# Sens_rler.net
KiCad netlist of a schematic drawn in Altium Designer
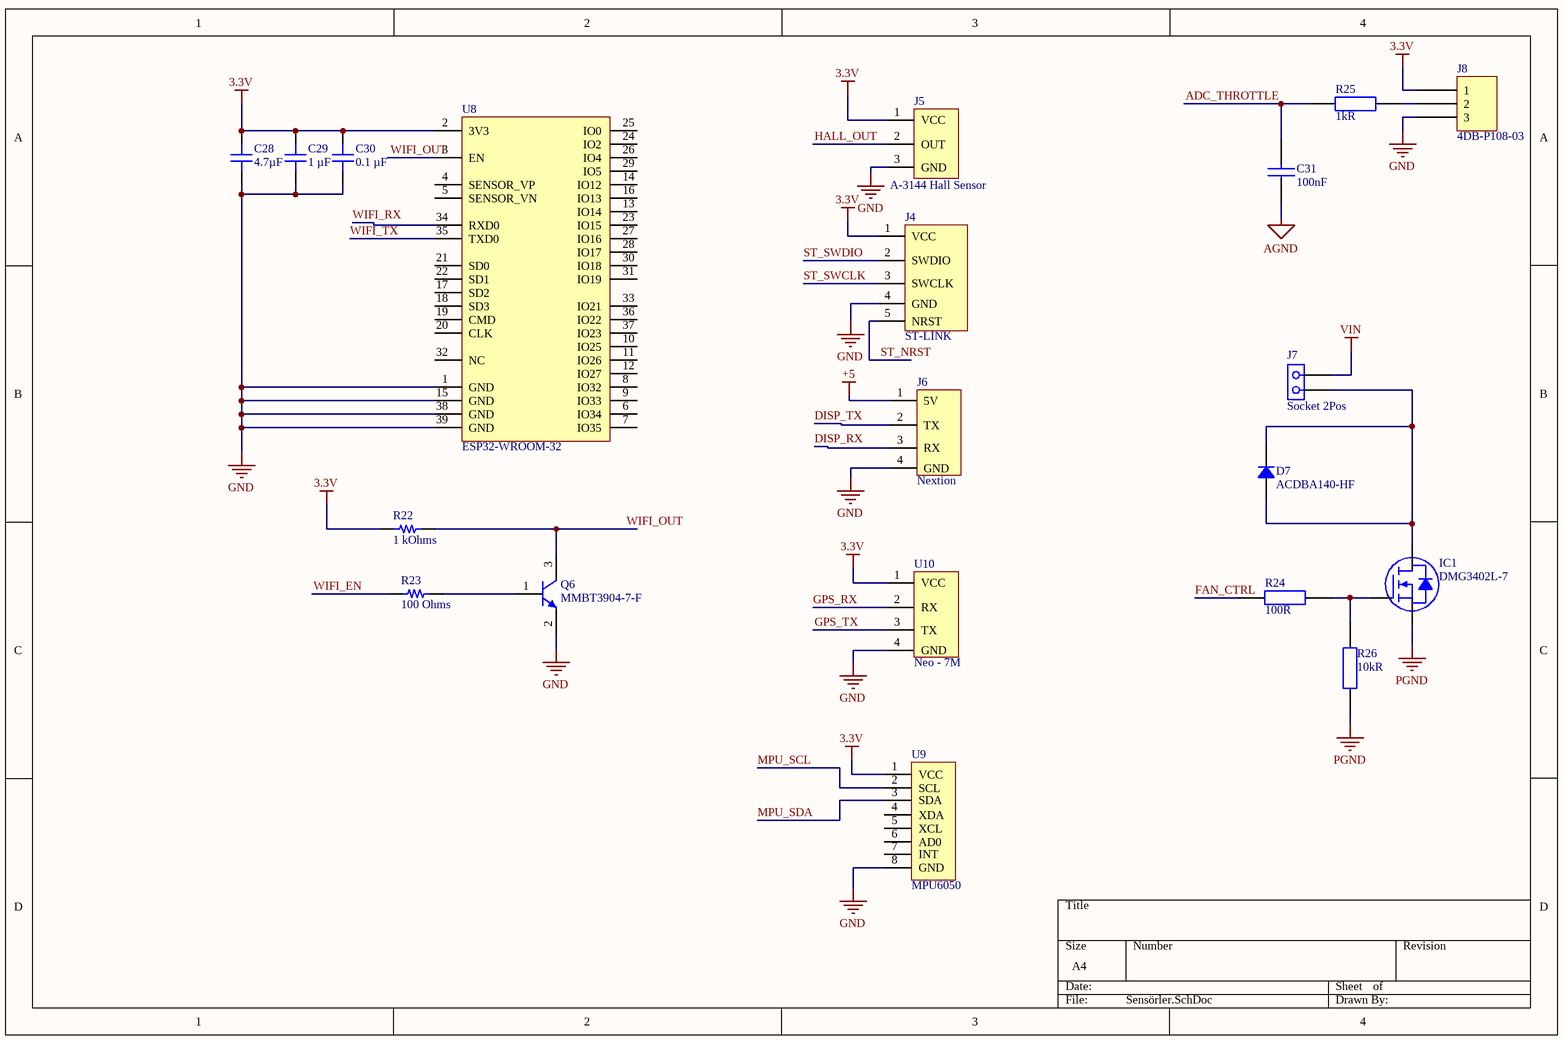
[diagram p0: Sensörler.SchDoc]

(export (version "E")
  (design (tool "Eeschema 10.0.6"))
  (components
    (comp (ref "C28")
      (value "4.7µF")
      (footprint "CAP 0805_2012")
      (description "CAP CER 4.7UF 16V X5R 0805")
      (fields
        (field (name "PART NUMBER") "0805YD475MAT2A")
        (field (name "CAPACITANCE") "4.7µF")
        (field (name "MANUFACTURER") "AVX Corporation")
      )
      (libsource (lib "Celestial Altium Library - altium_library") (part "Capacitor"))
    )
    (comp (ref "C29")
      (value "1 µF")
      (footprint "CAP 0805_2012")
      (description "CAP CER 1UF 16V X7R 0805")
      (fields
        (field (name "PART NUMBER") "EMK212B7105KGHTR")
        (field (name "CAPACITANCE") "1 µF")
        (field (name "MANUFACTURER") "Taiyo Yuden")
      )
      (libsource (lib "Celestial Altium Library - altium_library") (part "Capacitor"))
    )
    (comp (ref "C30")
      (value "0.1 µF")
      (footprint "CAP 0805_2012")
      (description "CAP CER 0.1UF 16V X7R 0805")
      (fields
        (field (name "PART NUMBER") "0805B104K160CT")
        (field (name "CAPACITANCE") "0.1 µF")
        (field (name "MANUFACTURER") "Walsin Technology Corporation")
      )
      (libsource (lib "Celestial Altium Library - altium_library") (part "Capacitor"))
    )
    (comp (ref "C31")
      (value "CL21B104KBCNNNC")
      (footprint "CAP_0805")
      (description "CAP CER 100nF %10 0805")
      (fields
        (field (name "MANUFACTURER") "Samsung")
        (field (name "TOLERANCE") "10%")
        (field (name "CAPACITANCE") "100nF")
        (field (name "DESIGNED BY") "BERK")
      )
      (libsource (lib "UDEMY_Library") (part "CAP CER 100nF 0805"))
    )
    (comp (ref "D7")
      (value "ACDBA140-HF")
      (footprint "DO214AC SMA")
      (description "DIODE SCHOTTKY 40V 1A DO214AC")
      (fields (field (name "MANUFACTURER") "Comchip Technology"))
      (libsource (lib "Celestial Altium Library - altium_library") (part "Diode"))
    )
    (comp (ref "IC1")
      (value "DMG3402L-7")
      (footprint "DIODES SOT-23-3")
      (description "MOSFET N-CH 30V 4A SOT23")
      (fields (field (name "MANUFACTURER") "Diodes Incorporated"))
      (libsource (lib "Celestial Altium Library - altium_library") (part "DIODES INC MOSFET N-CH SOT-23-3"))
    )
    (comp (ref "J4") (value "ST-LİNK") (footprint "ST-LİNK") (libsource (lib "TIDA_00620") (part "ST-LİNK")))
    (comp (ref "J5")
      (value "A-3144 Hall Sensor")
      (footprint "A-3144")
      (libsource (lib "TIDA_00620") (part "A-3144 Hall Sensor"))
    )
    (comp (ref "J6") (value "Nextion") (footprint "Nextion") (libsource (lib "TIDA_00620") (part "Nextion")))
    (comp (ref "J7")
      (value "Socket 2Pos")
      (footprint "691101710002")
      (description "Conn Terminal Block 2 POS 5mm Solder ST Thru-Hole 16A Box")
      (fields
        (field (name "MANUFACTURER") "Wurth Elektronik")
        (field (name "MANUFACTURER PART NUMBER") "691101710002")
      )
      (libsource (lib "TIDA_00620") (part "691 101 710 002"))
    )
    (comp (ref "J8")
      (value "4DB-P108-03")
      (footprint "TE 4DB-P108-03")
      (description "CONN BARRIER STRIP 3CIRC 0.325\"")
      (fields (field (name "MANUFACTURER") "TE Connectivity AMP Connectors"))
      (libsource (lib "Celestial Altium Library - altium_library") (part "3 Pin"))
    )
    (comp (ref "Q6")
      (value "MMBT3904-7-F")
      (footprint "DIODES SOT-23-3")
      (description "TRANS NPN 40V 0.2A SOT23-3")
      (fields (field (name "MANUFACTURER") "Diodes Incorporated"))
      (libsource (lib "Celestial Altium Library - altium_library") (part "DIODES INC NPN SOT-23-3"))
    )
    (comp (ref "R22")
      (value "1 kOhms")
      (footprint "RES 0603_1608")
      (description "RES SMD 1K OHM 0.1% 1/16W 0603")
      (fields
        (field (name "PART NUMBER") "CPF0603B1K0E")
        (field (name "MANUFACTURER") "TE Connectivity Passive Product")
      )
      (libsource (lib "Celestial Altium Library - altium_library") (part "Resistor"))
    )
    (comp (ref "R23")
      (value "100 Ohms")
      (footprint "RES 0402_1005")
      (description "RES 100 OHM 0.5% 1/5W 0402")
      (fields
        (field (name "PART NUMBER") "MCS0402PD1000DE500")
        (field (name "MANUFACTURER") "Vishay Beyschlag")
      )
      (libsource (lib "Celestial Altium Library - altium_library") (part "Resistor"))
    )
    (comp (ref "R24")
      (value "RC0603JR-07100RL")
      (footprint "RES_0603")
      (description "RES 100 %5 OHM 0603 SMD")
      (fields
        (field (name "MANUFACTURER") "Yageo")
        (field (name "TOLERANCE") "5%")
        (field (name "RESISTANCE") "100R")
        (field (name "DESIGNED BY") "BERK")
      )
      (libsource (lib "UDEMY_Library") (part "RES 100 OHM 0603"))
    )
    (comp (ref "R25")
      (value "RC0603FR-0710KL")
      (footprint "RES_0603")
      (description "RES 1K %1 OHM 0603 SMD")
      (fields
        (field (name "MANUFACTURER") "Yageo")
        (field (name "MANUFACTURER PART NUMBER") "RC0603JR-071KL")
        (field (name "RESISTANCE") "1kR")
        (field (name "DESIGNED BY") "BERK")
      )
      (libsource (lib "UDEMY_Library") (part "RES 1K OHM 0603"))
    )
    (comp (ref "R26")
      (value "RC0603FR-0710KL")
      (footprint "RES_0603")
      (description "RES 10K %1 OHM 0603 SMD")
      (fields
        (field (name "MANUFACTURER") "Yageo")
        (field (name "TOLERANCE") "1%")
        (field (name "RESISTANCE") "10kR")
        (field (name "DESIGNED BY") "BERK")
      )
      (libsource (lib "UDEMY_Library") (part "RES 10K OHM 0603"))
    )
    (comp (ref "U8")
      (value "ESP32-WROOM-32")
      (footprint "ESP32-32")
      (libsource (lib "TIDA_00620") (part "ESP32-WROOM-32"))
    )
    (comp (ref "U9")
      (value "MPU6050")
      (footprint "MPU6050")
      (description "IMU (Inertial Measurement Unit), 6-Axis, Accelerometer, Gyroscope")
      (fields (field (name "MANUFACTURER") "InvenSense") (field (name "MANUFACTURER PART NUMBER") "MPU-6050"))
      (libsource (lib "TIDA_00620") (part "MPU6050"))
    )
    (comp (ref "U10")
      (value "Neo - 7M")
      (footprint "Neo - 7M")
      (libsource (lib "TIDA_00620") (part "Neo - 7M"))
    )
  )
  (nets
    (net (code "1") (name "+5") (class "Default")
      (node (ref "J6") (pin "1") (pinfunction "5V_1") (pintype "power_in"))
    )
    (net (code "2") (name "/ADC_THROTTLE") (class "Default")
      (node (ref "C31") (pin "2") (pinfunction "2_2") (pintype "passive"))
      (node (ref "R25") (pin "1") (pinfunction "1_1") (pintype "passive"))
    )
    (net (code "3") (name "/DISP_RX") (class "Default")
      (node (ref "J6") (pin "3") (pinfunction "RX_3") (pintype "passive"))
    )
    (net (code "4") (name "/DISP_TX") (class "Default")
      (node (ref "J6") (pin "2") (pinfunction "TX_2") (pintype "passive"))
    )
    (net (code "5") (name "/FAN_CTRL") (class "Default")
      (node (ref "R24") (pin "1") (pinfunction "1_1") (pintype "passive"))
    )
    (net (code "6") (name "/GPS_RX") (class "Default")
      (node (ref "U10") (pin "2") (pinfunction "RX_2") (pintype "passive"))
    )
    (net (code "7") (name "/GPS_TX") (class "Default")
      (node (ref "U10") (pin "3") (pinfunction "TX_3") (pintype "passive"))
    )
    (net (code "8") (name "/HALL_OUT") (class "Default")
      (node (ref "J5") (pin "2") (pinfunction "OUT_2") (pintype "passive"))
    )
    (net (code "9") (name "/MPU_SCL") (class "Default")
      (node (ref "U9") (pin "2") (pinfunction "SCL_2") (pintype "passive"))
    )
    (net (code "10") (name "/MPU_SDA") (class "Default")
      (node (ref "U9") (pin "3") (pinfunction "SDA_3") (pintype "passive"))
    )
    (net (code "11") (name "/ST_NRST") (class "Default")
      (node (ref "J4") (pin "5") (pinfunction "NRST_5") (pintype "passive"))
    )
    (net (code "12") (name "/ST_SWCLK") (class "Default")
      (node (ref "J4") (pin "3") (pinfunction "SWCLK_3") (pintype "passive"))
    )
    (net (code "13") (name "/ST_SWDIO") (class "Default")
      (node (ref "J4") (pin "2") (pinfunction "SWDIO_2") (pintype "passive"))
    )
    (net (code "14") (name "/WIFI_EN") (class "Default")
      (node (ref "R23") (pin "1") (pinfunction "1_1") (pintype "passive"))
    )
    (net (code "15") (name "/WIFI_OUT") (class "Default")
      (node (ref "Q6") (pin "3") (pinfunction "C_3") (pintype "passive"))
      (node (ref "R22") (pin "2") (pinfunction "2_2") (pintype "passive"))
      (node (ref "U8") (pin "3") (pinfunction "EN_3") (pintype "passive"))
    )
    (net (code "16") (name "/WIFI_RX") (class "Default")
      (node (ref "U8") (pin "34") (pinfunction "RXD0_34") (pintype "passive"))
    )
    (net (code "17") (name "/WIFI_TX") (class "Default")
      (node (ref "U8") (pin "35") (pinfunction "TXD0_35") (pintype "passive"))
    )
    (net (code "18") (name "3.3V") (class "Default")
      (node (ref "C28") (pin "2") (pinfunction "2_2") (pintype "passive"))
      (node (ref "C29") (pin "2") (pinfunction "2_2") (pintype "passive"))
      (node (ref "C30") (pin "2") (pinfunction "2_2") (pintype "passive"))
      (node (ref "J4") (pin "1") (pinfunction "VCC_1") (pintype "passive"))
      (node (ref "J5") (pin "1") (pinfunction "VCC_1") (pintype "passive"))
      (node (ref "J8") (pin "1") (pinfunction "1_1") (pintype "passive"))
      (node (ref "R22") (pin "1") (pinfunction "1_1") (pintype "passive"))
      (node (ref "U10") (pin "1") (pinfunction "VCC_1") (pintype "passive"))
      (node (ref "U8") (pin "2") (pinfunction "3V3_2") (pintype "passive"))
      (node (ref "U9") (pin "1") (pinfunction "VCC_1") (pintype "power_in"))
    )
    (net (code "19") (name "AGND") (class "Default")
      (node (ref "C31") (pin "1") (pinfunction "1_1") (pintype "passive"))
    )
    (net (code "20") (name "GND") (class "Default")
      (node (ref "C28") (pin "1") (pinfunction "1_1") (pintype "passive"))
      (node (ref "C29") (pin "1") (pinfunction "1_1") (pintype "passive"))
      (node (ref "C30") (pin "1") (pinfunction "1_1") (pintype "passive"))
      (node (ref "J4") (pin "4") (pinfunction "GND_4") (pintype "passive"))
      (node (ref "J5") (pin "3") (pinfunction "GND_3") (pintype "passive"))
      (node (ref "J6") (pin "4") (pinfunction "GND_4") (pintype "passive"))
      (node (ref "J8") (pin "3") (pinfunction "3_3") (pintype "passive"))
      (node (ref "Q6") (pin "2") (pinfunction "E_2") (pintype "passive"))
      (node (ref "U10") (pin "4") (pinfunction "GND_4") (pintype "passive"))
      (node (ref "U8") (pin "1") (pinfunction "GND_1") (pintype "passive"))
      (node (ref "U8") (pin "15") (pinfunction "GND_15") (pintype "passive"))
      (node (ref "U8") (pin "38") (pinfunction "GND_38") (pintype "passive"))
      (node (ref "U8") (pin "39") (pinfunction "GND_39") (pintype "passive"))
      (node (ref "U9") (pin "8") (pinfunction "GND_8") (pintype "power_in"))
    )
    (net (code "21") (name "Net-(IC1-D)") (class "Default")
      (node (ref "D7") (pin "1") (pinfunction "1_1") (pintype "passive"))
      (node (ref "D7") (pin "2") (pinfunction "2_2") (pintype "passive"))
      (node (ref "IC1") (pin "3") (pinfunction "D_3") (pintype "passive"))
      (node (ref "J7") (pin "1") (pinfunction "1_1") (pintype "passive"))
    )
    (net (code "22") (name "Net-(IC1-G)") (class "Default")
      (node (ref "IC1") (pin "1") (pinfunction "G_1") (pintype "passive"))
      (node (ref "R24") (pin "2") (pinfunction "2_2") (pintype "passive"))
      (node (ref "R26") (pin "2") (pinfunction "2_2") (pintype "passive"))
    )
    (net (code "23") (name "Net-(J8-Pad2)") (class "Default")
      (node (ref "J8") (pin "2") (pinfunction "2_2") (pintype "passive"))
      (node (ref "R25") (pin "2") (pinfunction "2_2") (pintype "passive"))
    )
    (net (code "24") (name "Net-(Q6-B)") (class "Default")
      (node (ref "Q6") (pin "1") (pinfunction "B_1") (pintype "passive"))
      (node (ref "R23") (pin "2") (pinfunction "2_2") (pintype "passive"))
    )
    (net (code "25") (name "PGND") (class "Default")
      (node (ref "IC1") (pin "2") (pinfunction "S_2") (pintype "passive"))
      (node (ref "R26") (pin "1") (pinfunction "1_1") (pintype "passive"))
    )
    (net (code "26") (name "VIN") (class "Default")
      (node (ref "J7") (pin "2") (pinfunction "2_2") (pintype "passive"))
    )
    (net (code "27") (name "unconnected-(U8-CLK-Pad20)") (class "Default")
      (node (ref "U8") (pin "20") (pinfunction "CLK_20") (pintype "passive"))
    )
    (net (code "28") (name "unconnected-(U8-CMD-Pad19)") (class "Default")
      (node (ref "U8") (pin "19") (pinfunction "CMD_19") (pintype "passive"))
    )
    (net (code "29") (name "unconnected-(U8-IO0-Pad25)") (class "Default")
      (node (ref "U8") (pin "25") (pinfunction "IO0_25") (pintype "passive"))
    )
    (net (code "30") (name "unconnected-(U8-IO2-Pad24)") (class "Default")
      (node (ref "U8") (pin "24") (pinfunction "IO2_24") (pintype "passive"))
    )
    (net (code "31") (name "unconnected-(U8-IO4-Pad26)") (class "Default")
      (node (ref "U8") (pin "26") (pinfunction "IO4_26") (pintype "passive"))
    )
    (net (code "32") (name "unconnected-(U8-IO5-Pad29)") (class "Default")
      (node (ref "U8") (pin "29") (pinfunction "IO5_29") (pintype "passive"))
    )
    (net (code "33") (name "unconnected-(U8-IO12-Pad14)") (class "Default")
      (node (ref "U8") (pin "14") (pinfunction "IO12_14") (pintype "passive"))
    )
    (net (code "34") (name "unconnected-(U8-IO13-Pad16)") (class "Default")
      (node (ref "U8") (pin "16") (pinfunction "IO13_16") (pintype "passive"))
    )
    (net (code "35") (name "unconnected-(U8-IO14-Pad13)") (class "Default")
      (node (ref "U8") (pin "13") (pinfunction "IO14_13") (pintype "passive"))
    )
    (net (code "36") (name "unconnected-(U8-IO15-Pad23)") (class "Default")
      (node (ref "U8") (pin "23") (pinfunction "IO15_23") (pintype "passive"))
    )
    (net (code "37") (name "unconnected-(U8-IO16-Pad27)") (class "Default")
      (node (ref "U8") (pin "27") (pinfunction "IO16_27") (pintype "passive"))
    )
    (net (code "38") (name "unconnected-(U8-IO17-Pad28)") (class "Default")
      (node (ref "U8") (pin "28") (pinfunction "IO17_28") (pintype "passive"))
    )
    (net (code "39") (name "unconnected-(U8-IO18-Pad30)") (class "Default")
      (node (ref "U8") (pin "30") (pinfunction "IO18_30") (pintype "passive"))
    )
    (net (code "40") (name "unconnected-(U8-IO19-Pad31)") (class "Default")
      (node (ref "U8") (pin "31") (pinfunction "IO19_31") (pintype "passive"))
    )
    (net (code "41") (name "unconnected-(U8-IO21-Pad33)") (class "Default")
      (node (ref "U8") (pin "33") (pinfunction "IO21_33") (pintype "passive"))
    )
    (net (code "42") (name "unconnected-(U8-IO22-Pad36)") (class "Default")
      (node (ref "U8") (pin "36") (pinfunction "IO22_36") (pintype "passive"))
    )
    (net (code "43") (name "unconnected-(U8-IO23-Pad37)") (class "Default")
      (node (ref "U8") (pin "37") (pinfunction "IO23_37") (pintype "passive"))
    )
    (net (code "44") (name "unconnected-(U8-IO25-Pad10)") (class "Default")
      (node (ref "U8") (pin "10") (pinfunction "IO25_10") (pintype "passive"))
    )
    (net (code "45") (name "unconnected-(U8-IO26-Pad11)") (class "Default")
      (node (ref "U8") (pin "11") (pinfunction "IO26_11") (pintype "passive"))
    )
    (net (code "46") (name "unconnected-(U8-IO27-Pad12)") (class "Default")
      (node (ref "U8") (pin "12") (pinfunction "IO27_12") (pintype "passive"))
    )
    (net (code "47") (name "unconnected-(U8-IO32-Pad8)") (class "Default")
      (node (ref "U8") (pin "8") (pinfunction "IO32_8") (pintype "passive"))
    )
    (net (code "48") (name "unconnected-(U8-IO33-Pad9)") (class "Default")
      (node (ref "U8") (pin "9") (pinfunction "IO33_9") (pintype "passive"))
    )
    (net (code "49") (name "unconnected-(U8-IO34-Pad6)") (class "Default")
      (node (ref "U8") (pin "6") (pinfunction "IO34_6") (pintype "passive"))
    )
    (net (code "50") (name "unconnected-(U8-IO35-Pad7)") (class "Default")
      (node (ref "U8") (pin "7") (pinfunction "IO35_7") (pintype "passive"))
    )
    (net (code "51") (name "unconnected-(U8-NC-Pad32)") (class "Default")
      (node (ref "U8") (pin "32") (pinfunction "NC_32") (pintype "passive"))
    )
    (net (code "52") (name "unconnected-(U8-SD0-Pad21)") (class "Default")
      (node (ref "U8") (pin "21") (pinfunction "SD0_21") (pintype "passive"))
    )
    (net (code "53") (name "unconnected-(U8-SD1-Pad22)") (class "Default")
      (node (ref "U8") (pin "22") (pinfunction "SD1_22") (pintype "passive"))
    )
    (net (code "54") (name "unconnected-(U8-SD2-Pad17)") (class "Default")
      (node (ref "U8") (pin "17") (pinfunction "SD2_17") (pintype "passive"))
    )
    (net (code "55") (name "unconnected-(U8-SD3-Pad18)") (class "Default")
      (node (ref "U8") (pin "18") (pinfunction "SD3_18") (pintype "passive"))
    )
    (net (code "56") (name "unconnected-(U8-SENSOR_VN-Pad5)") (class "Default")
      (node (ref "U8") (pin "5") (pinfunction "SENSOR_VN_5") (pintype "passive"))
    )
    (net (code "57") (name "unconnected-(U8-SENSOR_VP-Pad4)") (class "Default")
      (node (ref "U8") (pin "4") (pinfunction "SENSOR_VP_4") (pintype "passive"))
    )
    (net (code "58") (name "unconnected-(U9-AD0-Pad6)") (class "Default")
      (node (ref "U9") (pin "6") (pinfunction "AD0_6") (pintype "passive"))
    )
    (net (code "59") (name "unconnected-(U9-INT-Pad7)") (class "Default")
      (node (ref "U9") (pin "7") (pinfunction "INT_7") (pintype "passive"))
    )
    (net (code "60") (name "unconnected-(U9-XCL-Pad5)") (class "Default")
      (node (ref "U9") (pin "5") (pinfunction "XCL_5") (pintype "passive"))
    )
    (net (code "61") (name "unconnected-(U9-XDA-Pad4)") (class "Default")
      (node (ref "U9") (pin "4") (pinfunction "XDA_4") (pintype "passive"))
    )
  )
)
